# subckt_LNA_HMC8410.net
KiCad netlist of a schematic drawn in Altium Designer
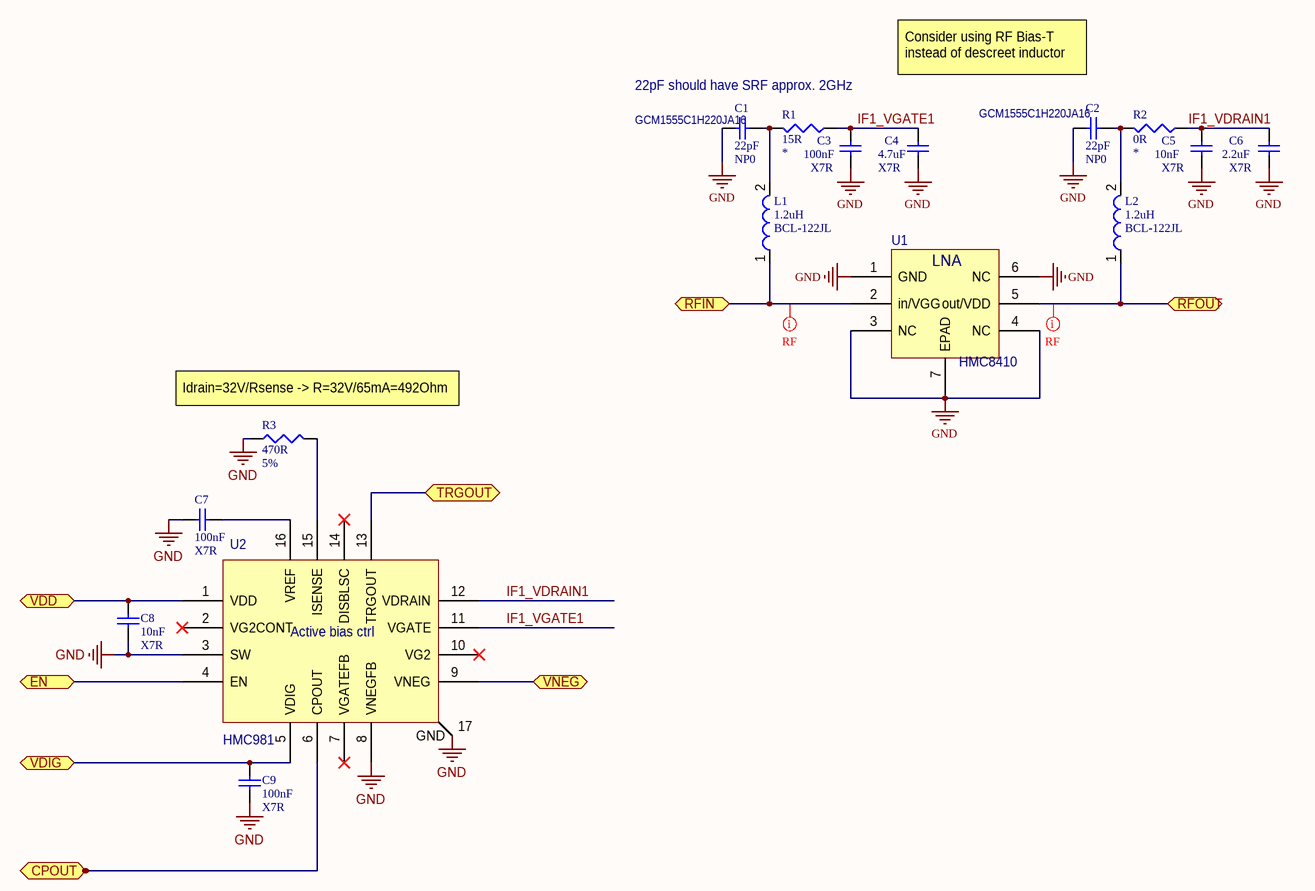
[diagram p0: subckt_LNA_HMC8410.SchDoc]

(export (version "E")
  (design (tool "Eeschema 10.0.6"))
  (components
    (comp (ref "C1")
      (value "22pF")
      (footprint "CAP0402")
      (description "Capacitor")
      (fields (field (name "DIELECTRIC") "NP0") (field (name "MODEL") "GCM1555C1H220JA16"))
      (libsource (lib "lib_basic") (part "Capacitor"))
    )
    (comp (ref "C2")
      (value "22pF")
      (footprint "CAP0402")
      (description "Capacitor")
      (fields (field (name "DIELECTRIC") "NP0") (field (name "MODEL") "GCM1555C1H220JA16"))
      (libsource (lib "lib_basic") (part "Capacitor"))
    )
    (comp (ref "C3")
      (value "100nF")
      (footprint "CAP0603")
      (description "Capacitor")
      (fields (field (name "DIELECTRIC") "X7R"))
      (libsource (lib "lib_basic") (part "Capacitor"))
    )
    (comp (ref "C4")
      (value "4.7uF")
      (footprint "CAP0603")
      (description "Capacitor")
      (fields (field (name "DIELECTRIC") "X7R"))
      (libsource (lib "lib_basic") (part "Capacitor"))
    )
    (comp (ref "C5")
      (value "10nF")
      (footprint "CAP0603")
      (description "Capacitor")
      (fields (field (name "DIELECTRIC") "X7R"))
      (libsource (lib "lib_basic") (part "Capacitor"))
    )
    (comp (ref "C6")
      (value "2.2uF")
      (footprint "CAP0603")
      (description "Capacitor")
      (fields (field (name "DIELECTRIC") "X7R"))
      (libsource (lib "lib_basic") (part "Capacitor"))
    )
    (comp (ref "C7")
      (value "100nF")
      (footprint "CAP0603")
      (description "Capacitor")
      (fields (field (name "DIELECTRIC") "X7R"))
      (libsource (lib "lib_basic") (part "Capacitor"))
    )
    (comp (ref "C8")
      (value "10nF")
      (footprint "CAP0603")
      (description "Capacitor")
      (fields (field (name "DIELECTRIC") "X7R"))
      (libsource (lib "lib_basic") (part "Capacitor"))
    )
    (comp (ref "C9")
      (value "100nF")
      (footprint "CAP0603")
      (description "Capacitor")
      (fields (field (name "DIELECTRIC") "X7R"))
      (libsource (lib "lib_basic") (part "Capacitor"))
    )
    (comp (ref "L1")
      (value "1.2uH")
      (footprint "lib_RF:Coilcraft_BCL-122")
      (description "Inductor")
      (fields (field (name "MODEL") "BCL-122JL"))
      (libsource (lib "lib_basic") (part "Inductor"))
    )
    (comp (ref "L2")
      (value "1.2uH")
      (footprint "lib_RF:Coilcraft_BCL-122")
      (description "Inductor")
      (fields (field (name "MODEL") "BCL-122JL"))
      (libsource (lib "lib_basic") (part "Inductor"))
    )
    (comp (ref "R1")
      (value "15R")
      (footprint "RES0603")
      (description "Resistor")
      (fields (field (name "TYPE") "*"))
      (libsource (lib "lib_basic") (part "Resistor"))
    )
    (comp (ref "R2")
      (value "0R")
      (footprint "RES0603")
      (description "Resistor")
      (fields (field (name "TYPE") "*"))
      (libsource (lib "lib_basic") (part "Resistor"))
    )
    (comp (ref "R3")
      (value "470R")
      (footprint "RES0603")
      (description "Resistor")
      (fields (field (name "TYPE") "5%"))
      (libsource (lib "lib_basic") (part "Resistor"))
    )
    (comp (ref "U1")
      (value "HMC8410")
      (description "0.01GHz-10GHz LNA")
      (libsource (lib "lib_RF_actives") (part "AD_HMC8410"))
    )
    (comp (ref "U2")
      (value "HMC981")
      (description "HMC981LP3E active bias controller for LNA's w/ external Vgg control")
      (libsource (lib "lib_RF_actives") (part "AD_HMC981LP3E"))
    )
  )
  (nets
    (net (code "1") (name "/CPOUT") (class "Default")
      (node (ref "U2") (pin "6") (pinfunction "CPOUT_6") (pintype "passive"))
    )
    (net (code "2") (name "/EN") (class "Default")
      (node (ref "U2") (pin "4") (pinfunction "EN_4") (pintype "passive"))
    )
    (net (code "3") (name "/IF1_VDRAIN1") (class "Default")
      (node (ref "C5") (pin "2") (pinfunction "2_2") (pintype "passive"))
      (node (ref "C6") (pin "2") (pinfunction "2_2") (pintype "passive"))
      (node (ref "R2") (pin "1") (pinfunction "1_1") (pintype "passive"))
      (node (ref "U2") (pin "12") (pinfunction "VDRAIN_12") (pintype "passive"))
    )
    (net (code "4") (name "/IF1_VGATE1") (class "Default")
      (node (ref "C3") (pin "2") (pinfunction "2_2") (pintype "passive"))
      (node (ref "C4") (pin "2") (pinfunction "2_2") (pintype "passive"))
      (node (ref "R1") (pin "1") (pinfunction "1_1") (pintype "passive"))
      (node (ref "U2") (pin "11") (pinfunction "VGATE_11") (pintype "passive"))
    )
    (net (code "5") (name "/RFIN") (class "Default")
      (node (ref "L1") (pin "1") (pinfunction "1_1") (pintype "passive"))
      (node (ref "U1") (pin "2") (pinfunction "in/VGG_2") (pintype "passive"))
    )
    (net (code "6") (name "/RFOUT") (class "Default")
      (node (ref "L2") (pin "1") (pinfunction "1_1") (pintype "passive"))
      (node (ref "U1") (pin "5") (pinfunction "out/VDD_5") (pintype "passive"))
    )
    (net (code "7") (name "/TRGOUT") (class "Default")
      (node (ref "U2") (pin "13") (pinfunction "TRGOUT_13") (pintype "passive"))
    )
    (net (code "8") (name "/VDD") (class "Default")
      (node (ref "C8") (pin "2") (pinfunction "2_2") (pintype "passive"))
      (node (ref "U2") (pin "1") (pinfunction "VDD_1") (pintype "passive"))
    )
    (net (code "9") (name "/VDIG") (class "Default")
      (node (ref "C9") (pin "2") (pinfunction "2_2") (pintype "passive"))
      (node (ref "U2") (pin "5") (pinfunction "VDIG_5") (pintype "passive"))
    )
    (net (code "10") (name "/VNEG") (class "Default")
      (node (ref "U2") (pin "9") (pinfunction "VNEG_9") (pintype "passive"))
    )
    (net (code "11") (name "GND") (class "Default")
      (node (ref "C1") (pin "2") (pinfunction "2_2") (pintype "passive"))
      (node (ref "C2") (pin "1") (pinfunction "1_1") (pintype "passive"))
      (node (ref "C3") (pin "1") (pinfunction "1_1") (pintype "passive"))
      (node (ref "C4") (pin "1") (pinfunction "1_1") (pintype "passive"))
      (node (ref "C5") (pin "1") (pinfunction "1_1") (pintype "passive"))
      (node (ref "C6") (pin "1") (pinfunction "1_1") (pintype "passive"))
      (node (ref "C7") (pin "1") (pinfunction "1_1") (pintype "passive"))
      (node (ref "C8") (pin "1") (pinfunction "1_1") (pintype "passive"))
      (node (ref "C9") (pin "1") (pinfunction "1_1") (pintype "passive"))
      (node (ref "R3") (pin "1") (pinfunction "1_1") (pintype "passive"))
      (node (ref "U1") (pin "1") (pinfunction "GND_1") (pintype "passive"))
      (node (ref "U1") (pin "3") (pinfunction "NC_3") (pintype "passive"))
      (node (ref "U1") (pin "4") (pinfunction "NC_4") (pintype "passive"))
      (node (ref "U1") (pin "6") (pinfunction "NC_6") (pintype "passive"))
      (node (ref "U1") (pin "7") (pinfunction "EPAD_7") (pintype "passive"))
      (node (ref "U2") (pin "17") (pinfunction "GND_17") (pintype "passive"))
      (node (ref "U2") (pin "3") (pinfunction "SW_3") (pintype "passive"))
      (node (ref "U2") (pin "8") (pinfunction "VNEGFB_8") (pintype "passive"))
    )
    (net (code "12") (name "Net-(C1-Pad1)") (class "Default")
      (node (ref "C1") (pin "1") (pinfunction "1_1") (pintype "passive"))
      (node (ref "L1") (pin "2") (pinfunction "2_2") (pintype "passive"))
      (node (ref "R1") (pin "2") (pinfunction "2_2") (pintype "passive"))
    )
    (net (code "13") (name "Net-(C2-Pad2)") (class "Default")
      (node (ref "C2") (pin "2") (pinfunction "2_2") (pintype "passive"))
      (node (ref "L2") (pin "2") (pinfunction "2_2") (pintype "passive"))
      (node (ref "R2") (pin "2") (pinfunction "2_2") (pintype "passive"))
    )
    (net (code "14") (name "Net-(U2-ISENSE)") (class "Default")
      (node (ref "R3") (pin "2") (pinfunction "2_2") (pintype "passive"))
      (node (ref "U2") (pin "15") (pinfunction "ISENSE_15") (pintype "passive"))
    )
    (net (code "15") (name "Net-(U2-VREF)") (class "Default")
      (node (ref "C7") (pin "2") (pinfunction "2_2") (pintype "passive"))
      (node (ref "U2") (pin "16") (pinfunction "VREF_16") (pintype "passive"))
    )
    (net (code "16") (name "unconnected-(U2-DISBLSC-Pad14)") (class "Default")
      (node (ref "U2") (pin "14") (pinfunction "DISBLSC_14") (pintype "passive+no_connect"))
    )
    (net (code "17") (name "unconnected-(U2-VG2-Pad10)") (class "Default")
      (node (ref "U2") (pin "10") (pinfunction "VG2_10") (pintype "passive+no_connect"))
    )
    (net (code "18") (name "unconnected-(U2-VG2CONT-Pad2)") (class "Default")
      (node (ref "U2") (pin "2") (pinfunction "VG2CONT_2") (pintype "passive+no_connect"))
    )
    (net (code "19") (name "unconnected-(U2-VGATEFB-Pad7)") (class "Default")
      (node (ref "U2") (pin "7") (pinfunction "VGATEFB_7") (pintype "passive+no_connect"))
    )
  )
)
